# BMS_REV_A1.net
KiCad netlist of a schematic drawn in Altium Designer
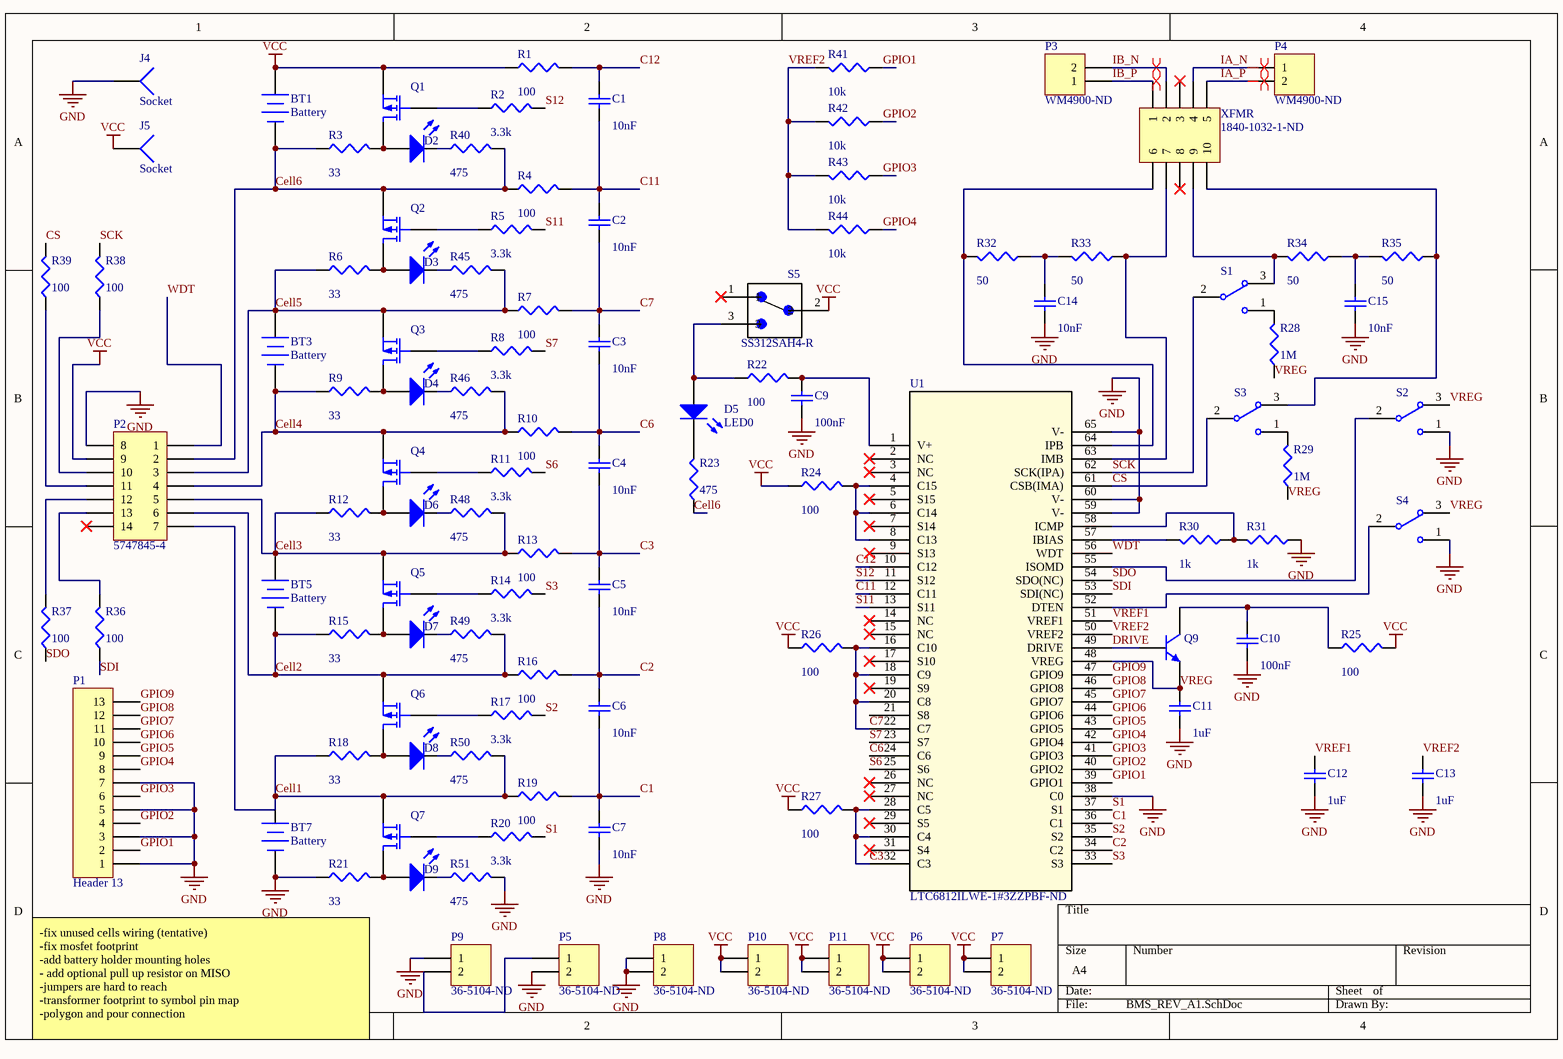
[diagram p0: BMS_REV_A1.SchDoc]

(export (version "E")
  (design (tool "Eeschema 10.0.6"))
  (components
    (comp (ref "BT1")
      (value "Battery")
      (footprint "18650 SMD:PCBComponent_1")
      (description "Multicell Battery")
      (fields (field (name "PUBLISHER") "Altium Limited"))
      (libsource (lib "Miscellaneous Devices") (part "Battery"))
    )
    (comp (ref "BT3")
      (value "Battery")
      (footprint "18650 SMD:PCBComponent_1")
      (description "Multicell Battery")
      (fields (field (name "PUBLISHER") "Altium Limited"))
      (libsource (lib "Miscellaneous Devices") (part "Battery"))
    )
    (comp (ref "BT5")
      (value "Battery")
      (footprint "18650 SMD:PCBComponent_1")
      (description "Multicell Battery")
      (fields (field (name "PUBLISHER") "Altium Limited"))
      (libsource (lib "Miscellaneous Devices") (part "Battery"))
    )
    (comp (ref "BT7")
      (value "Battery")
      (footprint "18650 SMD:PCBComponent_1")
      (description "Multicell Battery")
      (fields (field (name "PUBLISHER") "Altium Limited"))
      (libsource (lib "Miscellaneous Devices") (part "Battery"))
    )
    (comp (ref "C1")
      (value "10nF")
      (footprint "1608[0603]")
      (description "Capacitor (Semiconductor SIM Model)")
      (fields (field (name "Comment") "399-1092-1-ND") (field (name "PUBLISHER") "Altium Limited"))
      (libsource (lib "Miscellaneous Devices") (part "Cap Semi"))
    )
    (comp (ref "C2")
      (value "10nF")
      (footprint "1608[0603]")
      (description "Capacitor (Semiconductor SIM Model)")
      (fields (field (name "Comment") "399-1092-1-ND") (field (name "PUBLISHER") "Altium Limited"))
      (libsource (lib "Miscellaneous Devices") (part "Cap Semi"))
    )
    (comp (ref "C3")
      (value "10nF")
      (footprint "1608[0603]")
      (description "Capacitor (Semiconductor SIM Model)")
      (fields (field (name "Comment") "399-1092-1-ND") (field (name "PUBLISHER") "Altium Limited"))
      (libsource (lib "Miscellaneous Devices") (part "Cap Semi"))
    )
    (comp (ref "C4")
      (value "10nF")
      (footprint "1608[0603]")
      (description "Capacitor (Semiconductor SIM Model)")
      (fields (field (name "Comment") "399-1092-1-ND") (field (name "PUBLISHER") "Altium Limited"))
      (libsource (lib "Miscellaneous Devices") (part "Cap Semi"))
    )
    (comp (ref "C5")
      (value "10nF")
      (footprint "1608[0603]")
      (description "Capacitor (Semiconductor SIM Model)")
      (fields (field (name "Comment") "399-1092-1-ND") (field (name "PUBLISHER") "Altium Limited"))
      (libsource (lib "Miscellaneous Devices") (part "Cap Semi"))
    )
    (comp (ref "C6")
      (value "10nF")
      (footprint "1608[0603]")
      (description "Capacitor (Semiconductor SIM Model)")
      (fields (field (name "Comment") "399-1092-1-ND") (field (name "PUBLISHER") "Altium Limited"))
      (libsource (lib "Miscellaneous Devices") (part "Cap Semi"))
    )
    (comp (ref "C7")
      (value "10nF")
      (footprint "1608[0603]")
      (description "Capacitor (Semiconductor SIM Model)")
      (fields (field (name "Comment") "399-1092-1-ND") (field (name "PUBLISHER") "Altium Limited"))
      (libsource (lib "Miscellaneous Devices") (part "Cap Semi"))
    )
    (comp (ref "C9")
      (value "100nF")
      (footprint "6-0805_N")
      (description "Capacitor (Semiconductor SIM Model)")
      (fields (field (name "Comment") "1276-1090-1-ND") (field (name "PUBLISHER") "Altium Limited"))
      (libsource (lib "Miscellaneous Devices") (part "Cap Semi"))
    )
    (comp (ref "C10")
      (value "100nF")
      (footprint "6-0805_N")
      (description "Capacitor (Semiconductor SIM Model)")
      (fields (field (name "Comment") "1276-1090-1-ND") (field (name "PUBLISHER") "Altium Limited"))
      (libsource (lib "Miscellaneous Devices") (part "Cap Semi"))
    )
    (comp (ref "C11")
      (value "1uF")
      (footprint "6-0805_N")
      (description "Capacitor (Semiconductor SIM Model)")
      (fields (field (name "Comment") "311-3498-1-ND") (field (name "PUBLISHER") "Altium Limited"))
      (libsource (lib "Miscellaneous Devices") (part "Cap Semi"))
    )
    (comp (ref "C12")
      (value "1uF")
      (footprint "6-0805_N")
      (description "Capacitor (Semiconductor SIM Model)")
      (fields (field (name "Comment") "311-3498-1-ND") (field (name "PUBLISHER") "Altium Limited"))
      (libsource (lib "Miscellaneous Devices") (part "Cap Semi"))
    )
    (comp (ref "C13")
      (value "1uF")
      (footprint "6-0805_N")
      (description "Capacitor (Semiconductor SIM Model)")
      (fields (field (name "Comment") "311-3498-1-ND") (field (name "PUBLISHER") "Altium Limited"))
      (libsource (lib "Miscellaneous Devices") (part "Cap Semi"))
    )
    (comp (ref "C14")
      (value "10nF")
      (footprint "1608[0603]")
      (description "Capacitor (Semiconductor SIM Model)")
      (fields (field (name "Comment") "399-1092-1-ND") (field (name "PUBLISHER") "Altium Limited"))
      (libsource (lib "Miscellaneous Devices") (part "Cap Semi"))
    )
    (comp (ref "C15")
      (value "10nF")
      (footprint "1608[0603]")
      (description "Capacitor (Semiconductor SIM Model)")
      (fields (field (name "Comment") "399-1092-1-ND") (field (name "PUBLISHER") "Altium Limited"))
      (libsource (lib "Miscellaneous Devices") (part "Cap Semi"))
    )
    (comp (ref "D2")
      (value "160-1435-1-ND")
      (footprint "J1-0603")
      (description "Typical INFRARED GaAs LED")
      (fields (field (name "PUBLISHER") "Altium Limited"))
      (libsource (lib "Miscellaneous Devices") (part "LED0"))
    )
    (comp (ref "D3")
      (value "160-1435-1-ND")
      (footprint "J1-0603")
      (description "Typical INFRARED GaAs LED")
      (fields (field (name "PUBLISHER") "Altium Limited"))
      (libsource (lib "Miscellaneous Devices") (part "LED0"))
    )
    (comp (ref "D4")
      (value "160-1435-1-ND")
      (footprint "J1-0603")
      (description "Typical INFRARED GaAs LED")
      (fields (field (name "PUBLISHER") "Altium Limited"))
      (libsource (lib "Miscellaneous Devices") (part "LED0"))
    )
    (comp (ref "D5")
      (value "LED0")
      (footprint "J1-0603")
      (description "Typical INFRARED GaAs LED")
      (fields (field (name "PUBLISHER") "Altium Limited"))
      (libsource (lib "Miscellaneous Devices") (part "LED0"))
    )
    (comp (ref "D6")
      (value "160-1435-1-ND")
      (footprint "J1-0603")
      (description "Typical INFRARED GaAs LED")
      (fields (field (name "PUBLISHER") "Altium Limited"))
      (libsource (lib "Miscellaneous Devices") (part "LED0"))
    )
    (comp (ref "D7")
      (value "160-1435-1-ND")
      (footprint "J1-0603")
      (description "Typical INFRARED GaAs LED")
      (fields (field (name "PUBLISHER") "Altium Limited"))
      (libsource (lib "Miscellaneous Devices") (part "LED0"))
    )
    (comp (ref "D8")
      (value "160-1435-1-ND")
      (footprint "J1-0603")
      (description "Typical INFRARED GaAs LED")
      (fields (field (name "PUBLISHER") "Altium Limited"))
      (libsource (lib "Miscellaneous Devices") (part "LED0"))
    )
    (comp (ref "D9")
      (value "160-1435-1-ND")
      (footprint "J1-0603")
      (description "Typical INFRARED GaAs LED")
      (fields (field (name "PUBLISHER") "Altium Limited"))
      (libsource (lib "Miscellaneous Devices") (part "LED0"))
    )
    (comp (ref "J4")
      (value "Socket")
      (footprint "SMD Power Pad:PCBComponent_1")
      (fields (field (name "PUBLISHER") "Altium Limited"))
      (libsource (lib "Miscellaneous Connectors") (part "Socket"))
    )
    (comp (ref "J5")
      (value "Socket")
      (footprint "SMD Power Pad:PCBComponent_1")
      (fields (field (name "PUBLISHER") "Altium Limited"))
      (libsource (lib "Miscellaneous Connectors") (part "Socket"))
    )
    (comp (ref "P1")
      (value "Header 13")
      (footprint "SMD Finger Pads:PCBComponent_1")
      (description "Header, 13-Pin")
      (fields (field (name "PUBLISHER") "Altium Limited"))
      (libsource (lib "Miscellaneous Connectors") (part "Header 13"))
    )
    (comp (ref "P2")
      (value "5747845-4")
      (footprint "*5747845-4")
      (description "Header, 7-Pin, Dual row")
      (fields (field (name "PUBLISHER") "Altium Limited"))
      (libsource (lib "Miscellaneous Connectors") (part "Header 7X2A"))
    )
    (comp (ref "P3")
      (value "WM4900-ND")
      (footprint "Molex Connectors:WM4900-ND")
      (description "Header, 2-Pin")
      (fields (field (name "PUBLISHER") "Altium Limited"))
      (libsource (lib "") (part "Header 2_1"))
    )
    (comp (ref "P4")
      (value "WM4900-ND")
      (footprint "Molex Connectors:WM4900-ND")
      (description "Header, 2-Pin")
      (fields (field (name "PUBLISHER") "Altium Limited"))
      (libsource (lib "Miscellaneous Connectors") (part "Header 2"))
    )
    (comp (ref "P5")
      (value "36-5104-ND")
      (footprint "5104:PCBComponent_1")
      (description "Header, 2-Pin")
      (fields (field (name "PUBLISHER") "Altium Limited"))
      (libsource (lib "Miscellaneous Connectors") (part "Header 2"))
    )
    (comp (ref "P6")
      (value "36-5104-ND")
      (footprint "5104:PCBComponent_1")
      (description "Header, 2-Pin")
      (fields (field (name "PUBLISHER") "Altium Limited"))
      (libsource (lib "Miscellaneous Connectors") (part "Header 2"))
    )
    (comp (ref "P7")
      (value "36-5104-ND")
      (footprint "5104:PCBComponent_1")
      (description "Header, 2-Pin")
      (fields (field (name "PUBLISHER") "Altium Limited"))
      (libsource (lib "Miscellaneous Connectors") (part "Header 2"))
    )
    (comp (ref "P8")
      (value "36-5104-ND")
      (footprint "5104:PCBComponent_1")
      (description "Header, 2-Pin")
      (fields (field (name "PUBLISHER") "Altium Limited"))
      (libsource (lib "Miscellaneous Connectors") (part "Header 2"))
    )
    (comp (ref "P9")
      (value "36-5104-ND")
      (footprint "5104:PCBComponent_1")
      (description "Header, 2-Pin")
      (fields (field (name "PUBLISHER") "Altium Limited"))
      (libsource (lib "Miscellaneous Connectors") (part "Header 2"))
    )
    (comp (ref "P10")
      (value "36-5104-ND")
      (footprint "5104:PCBComponent_1")
      (description "Header, 2-Pin")
      (fields (field (name "PUBLISHER") "Altium Limited"))
      (libsource (lib "Miscellaneous Connectors") (part "Header 2"))
    )
    (comp (ref "P11")
      (value "36-5104-ND")
      (footprint "5104:PCBComponent_1")
      (description "Header, 2-Pin")
      (fields (field (name "PUBLISHER") "Altium Limited"))
      (libsource (lib "Miscellaneous Connectors") (part "Header 2"))
    )
    (comp (ref "Q1")
      (value "BSS308PEH6327XTSA1CT-ND")
      (footprint "SOT95P245X110-3N")
      (description "P-Channel MOSFET")
      (fields (field (name "PUBLISHER") "Altium Limited"))
      (libsource (lib "Miscellaneous Devices") (part "MOSFET-P"))
    )
    (comp (ref "Q2")
      (value "BSS308PEH6327XTSA1CT-ND")
      (footprint "SOT95P245X110-3N")
      (description "P-Channel MOSFET")
      (fields (field (name "PUBLISHER") "Altium Limited"))
      (libsource (lib "Miscellaneous Devices") (part "MOSFET-P"))
    )
    (comp (ref "Q3")
      (value "BSS308PEH6327XTSA1CT-ND")
      (footprint "SOT95P245X110-3N")
      (description "P-Channel MOSFET")
      (fields (field (name "PUBLISHER") "Altium Limited"))
      (libsource (lib "Miscellaneous Devices") (part "MOSFET-P"))
    )
    (comp (ref "Q4")
      (value "BSS308PEH6327XTSA1CT-ND")
      (footprint "SOT95P245X110-3N")
      (description "P-Channel MOSFET")
      (fields (field (name "PUBLISHER") "Altium Limited"))
      (libsource (lib "Miscellaneous Devices") (part "MOSFET-P"))
    )
    (comp (ref "Q5")
      (value "BSS308PEH6327XTSA1CT-ND")
      (footprint "SOT95P245X110-3N")
      (description "P-Channel MOSFET")
      (fields (field (name "PUBLISHER") "Altium Limited"))
      (libsource (lib "Miscellaneous Devices") (part "MOSFET-P"))
    )
    (comp (ref "Q6")
      (value "BSS308PEH6327XTSA1CT-ND")
      (footprint "SOT95P245X110-3N")
      (description "P-Channel MOSFET")
      (fields (field (name "PUBLISHER") "Altium Limited"))
      (libsource (lib "Miscellaneous Devices") (part "MOSFET-P"))
    )
    (comp (ref "Q7")
      (value "BSS308PEH6327XTSA1CT-ND")
      (footprint "SOT95P245X110-3N")
      (description "P-Channel MOSFET")
      (fields (field (name "PUBLISHER") "Altium Limited"))
      (libsource (lib "Miscellaneous Devices") (part "MOSFET-P"))
    )
    (comp (ref "Q9")
      (value "DXT5551P5-13CT-ND")
      (footprint "DXT5551P5-13")
      (description "NPN General Purpose Amplifier")
      (fields (field (name "PUBLISHER") "Altium Limited"))
      (libsource (lib "Miscellaneous Devices") (part "2N3904"))
    )
    (comp (ref "R1")
      (value "100")
      (footprint "J1-0603")
      (description "Resistor")
      (fields (field (name "Comment") "A129676CT-ND") (field (name "PUBLISHER") "Altium Limited"))
      (libsource (lib "Miscellaneous Devices") (part "Res3"))
    )
    (comp (ref "R2")
      (value "3.3k")
      (footprint "J1-0603")
      (description "Resistor")
      (fields (field (name "Comment") "A129543CT-ND") (field (name "PUBLISHER") "Altium Limited"))
      (libsource (lib "Miscellaneous Devices") (part "Res3"))
    )
    (comp (ref "R3")
      (value "33")
      (footprint "12Z-2010")
      (description "Resistor")
      (fields (field (name "Comment") "A130642CT-ND") (field (name "PUBLISHER") "Altium Limited"))
      (libsource (lib "Miscellaneous Devices") (part "Res3"))
    )
    (comp (ref "R4")
      (value "100")
      (footprint "J1-0603")
      (description "Resistor")
      (fields (field (name "Comment") "A129676CT-ND") (field (name "PUBLISHER") "Altium Limited"))
      (libsource (lib "Miscellaneous Devices") (part "Res3"))
    )
    (comp (ref "R5")
      (value "3.3k")
      (footprint "J1-0603")
      (description "Resistor")
      (fields (field (name "Comment") "A129543CT-ND") (field (name "PUBLISHER") "Altium Limited"))
      (libsource (lib "Miscellaneous Devices") (part "Res3"))
    )
    (comp (ref "R6")
      (value "33")
      (footprint "12Z-2010")
      (description "Resistor")
      (fields (field (name "Comment") "A130642CT-ND") (field (name "PUBLISHER") "Altium Limited"))
      (libsource (lib "Miscellaneous Devices") (part "Res3"))
    )
    (comp (ref "R7")
      (value "100")
      (footprint "J1-0603")
      (description "Resistor")
      (fields (field (name "Comment") "A129676CT-ND") (field (name "PUBLISHER") "Altium Limited"))
      (libsource (lib "Miscellaneous Devices") (part "Res3"))
    )
    (comp (ref "R8")
      (value "3.3k")
      (footprint "J1-0603")
      (description "Resistor")
      (fields (field (name "Comment") "A129543CT-ND") (field (name "PUBLISHER") "Altium Limited"))
      (libsource (lib "Miscellaneous Devices") (part "Res3"))
    )
    (comp (ref "R9")
      (value "33")
      (footprint "12Z-2010")
      (description "Resistor")
      (fields (field (name "Comment") "A130642CT-ND") (field (name "PUBLISHER") "Altium Limited"))
      (libsource (lib "Miscellaneous Devices") (part "Res3"))
    )
    (comp (ref "R10")
      (value "100")
      (footprint "J1-0603")
      (description "Resistor")
      (fields (field (name "Comment") "A129676CT-ND") (field (name "PUBLISHER") "Altium Limited"))
      (libsource (lib "Miscellaneous Devices") (part "Res3"))
    )
    (comp (ref "R11")
      (value "3.3k")
      (footprint "J1-0603")
      (description "Resistor")
      (fields (field (name "Comment") "A129543CT-ND") (field (name "PUBLISHER") "Altium Limited"))
      (libsource (lib "Miscellaneous Devices") (part "Res3"))
    )
    (comp (ref "R12")
      (value "33")
      (footprint "12Z-2010")
      (description "Resistor")
      (fields (field (name "Comment") "A130642CT-ND") (field (name "PUBLISHER") "Altium Limited"))
      (libsource (lib "Miscellaneous Devices") (part "Res3"))
    )
    (comp (ref "R13")
      (value "100")
      (footprint "J1-0603")
      (description "Resistor")
      (fields (field (name "Comment") "A129676CT-ND") (field (name "PUBLISHER") "Altium Limited"))
      (libsource (lib "Miscellaneous Devices") (part "Res3"))
    )
    (comp (ref "R14")
      (value "3.3k")
      (footprint "J1-0603")
      (description "Resistor")
      (fields (field (name "Comment") "A129543CT-ND") (field (name "PUBLISHER") "Altium Limited"))
      (libsource (lib "Miscellaneous Devices") (part "Res3"))
    )
    (comp (ref "R15")
      (value "33")
      (footprint "12Z-2010")
      (description "Resistor")
      (fields (field (name "Comment") "A130642CT-ND") (field (name "PUBLISHER") "Altium Limited"))
      (libsource (lib "Miscellaneous Devices") (part "Res3"))
    )
    (comp (ref "R16")
      (value "100")
      (footprint "J1-0603")
      (description "Resistor")
      (fields (field (name "Comment") "A129676CT-ND") (field (name "PUBLISHER") "Altium Limited"))
      (libsource (lib "Miscellaneous Devices") (part "Res3"))
    )
    (comp (ref "R17")
      (value "3.3k")
      (footprint "J1-0603")
      (description "Resistor")
      (fields (field (name "Comment") "A129543CT-ND") (field (name "PUBLISHER") "Altium Limited"))
      (libsource (lib "Miscellaneous Devices") (part "Res3"))
    )
    (comp (ref "R18")
      (value "33")
      (footprint "12Z-2010")
      (description "Resistor")
      (fields (field (name "Comment") "A130642CT-ND") (field (name "PUBLISHER") "Altium Limited"))
      (libsource (lib "Miscellaneous Devices") (part "Res3"))
    )
    (comp (ref "R19")
      (value "100")
      (footprint "J1-0603")
      (description "Resistor")
      (fields (field (name "Comment") "A129676CT-ND") (field (name "PUBLISHER") "Altium Limited"))
      (libsource (lib "Miscellaneous Devices") (part "Res3"))
    )
    (comp (ref "R20")
      (value "3.3k")
      (footprint "J1-0603")
      (description "Resistor")
      (fields (field (name "Comment") "A129543CT-ND") (field (name "PUBLISHER") "Altium Limited"))
      (libsource (lib "Miscellaneous Devices") (part "Res3"))
    )
    (comp (ref "R21")
      (value "33")
      (footprint "12Z-2010")
      (description "Resistor")
      (fields (field (name "Comment") "A130642CT-ND") (field (name "PUBLISHER") "Altium Limited"))
      (libsource (lib "Miscellaneous Devices") (part "Res3"))
    )
    (comp (ref "R22")
      (value "100")
      (footprint "J1-0603")
      (description "Resistor")
      (fields (field (name "Comment") "A129676CT-ND") (field (name "PUBLISHER") "Altium Limited"))
      (libsource (lib "Miscellaneous Devices") (part "Res3"))
    )
    (comp (ref "R23")
      (value "475")
      (footprint "J1-0603")
      (description "Resistor")
      (fields (field (name "Comment") "RMCF2010JT33R0CT-ND") (field (name "PUBLISHER") "Altium Limited"))
      (libsource (lib "Miscellaneous Devices") (part "Res3"))
    )
    (comp (ref "R24")
      (value "100")
      (footprint "J1-0603")
      (description "Resistor")
      (fields (field (name "Comment") "A129676CT-ND") (field (name "PUBLISHER") "Altium Limited"))
      (libsource (lib "Miscellaneous Devices") (part "Res3"))
    )
    (comp (ref "R25")
      (value "100")
      (footprint "J1-0603")
      (description "Resistor")
      (fields (field (name "Comment") "A129676CT-ND") (field (name "PUBLISHER") "Altium Limited"))
      (libsource (lib "Miscellaneous Devices") (part "Res3"))
    )
    (comp (ref "R26")
      (value "100")
      (footprint "J1-0603")
      (description "Resistor")
      (fields (field (name "Comment") "A129676CT-ND") (field (name "PUBLISHER") "Altium Limited"))
      (libsource (lib "Miscellaneous Devices") (part "Res3"))
    )
    (comp (ref "R27")
      (value "100")
      (footprint "J1-0603")
      (description "Resistor")
      (fields (field (name "Comment") "A129676CT-ND") (field (name "PUBLISHER") "Altium Limited"))
      (libsource (lib "Miscellaneous Devices") (part "Res3"))
    )
    (comp (ref "R28")
      (value "1M")
      (footprint "J1-0603")
      (description "Resistor")
      (fields (field (name "Comment") "A129724CT-ND") (field (name "PUBLISHER") "Altium Limited"))
      (libsource (lib "Miscellaneous Devices") (part "Res3"))
    )
    (comp (ref "R29")
      (value "1M")
      (footprint "J1-0603")
      (description "Resistor")
      (fields (field (name "Comment") "A129724CT-ND") (field (name "PUBLISHER") "Altium Limited"))
      (libsource (lib "Miscellaneous Devices") (part "Res3"))
    )
    (comp (ref "R30")
      (value "1k")
      (footprint "J1-0603")
      (description "Resistor")
      (fields (field (name "Comment") "RNCP0603FTD1K00CT-ND") (field (name "PUBLISHER") "Altium Limited"))
      (libsource (lib "Miscellaneous Devices") (part "Res3"))
    )
    (comp (ref "R31")
      (value "1k")
      (footprint "J1-0603")
      (description "Resistor")
      (fields (field (name "Comment") "RNCP0603FTD1K00CT-ND") (field (name "PUBLISHER") "Altium Limited"))
      (libsource (lib "Miscellaneous Devices") (part "Res3"))
    )
    (comp (ref "R32")
      (value "50")
      (footprint "J1-0603")
      (description "Resistor")
      (fields (field (name "Comment") "311-2598-1-ND") (field (name "PUBLISHER") "Altium Limited"))
      (libsource (lib "Miscellaneous Devices") (part "Res3"))
    )
    (comp (ref "R33")
      (value "50")
      (footprint "J1-0603")
      (description "Resistor")
      (fields (field (name "Comment") "311-2598-1-ND") (field (name "PUBLISHER") "Altium Limited"))
      (libsource (lib "Miscellaneous Devices") (part "Res3"))
    )
    (comp (ref "R34")
      (value "50")
      (footprint "J1-0603")
      (description "Resistor")
      (fields (field (name "Comment") "311-2598-1-ND") (field (name "PUBLISHER") "Altium Limited"))
      (libsource (lib "Miscellaneous Devices") (part "Res3"))
    )
    (comp (ref "R35")
      (value "50")
      (footprint "J1-0603")
      (description "Resistor")
      (fields (field (name "Comment") "311-2598-1-ND") (field (name "PUBLISHER") "Altium Limited"))
      (libsource (lib "Miscellaneous Devices") (part "Res3"))
    )
    (comp (ref "R36")
      (value "100")
      (footprint "J1-0603")
      (description "Resistor")
      (fields (field (name "Comment") "A129676CT-ND") (field (name "PUBLISHER") "Altium Limited"))
      (libsource (lib "Miscellaneous Devices") (part "Res3"))
    )
    (comp (ref "R37")
      (value "100")
      (footprint "J1-0603")
      (description "Resistor")
      (fields (field (name "Comment") "A129676CT-ND") (field (name "PUBLISHER") "Altium Limited"))
      (libsource (lib "Miscellaneous Devices") (part "Res3"))
    )
    (comp (ref "R38")
      (value "100")
      (footprint "J1-0603")
      (description "Resistor")
      (fields (field (name "Comment") "A129676CT-ND") (field (name "PUBLISHER") "Altium Limited"))
      (libsource (lib "Miscellaneous Devices") (part "Res3"))
    )
    (comp (ref "R39")
      (value "100")
      (footprint "J1-0603")
      (description "Resistor")
      (fields (field (name "Comment") "A129676CT-ND") (field (name "PUBLISHER") "Altium Limited"))
      (libsource (lib "Miscellaneous Devices") (part "Res3"))
    )
    (comp (ref "R40")
      (value "475")
      (footprint "J1-0603")
      (description "Resistor")
      (fields (field (name "Comment") "RMCF2010JT33R0CT-ND") (field (name "PUBLISHER") "Altium Limited"))
      (libsource (lib "Miscellaneous Devices") (part "Res3"))
    )
    (comp (ref "R41")
      (value "10k")
      (footprint "J1-0603")
      (description "Resistor")
      (fields (field (name "Comment") "RNCP0603FTD10K0CT-ND") (field (name "PUBLISHER") "Altium Limited"))
      (libsource (lib "Miscellaneous Devices") (part "Res3"))
    )
    (comp (ref "R42")
      (value "10k")
      (footprint "J1-0603")
      (description "Resistor")
      (fields (field (name "Comment") "RNCP0603FTD10K0CT-ND") (field (name "PUBLISHER") "Altium Limited"))
      (libsource (lib "Miscellaneous Devices") (part "Res3"))
    )
    (comp (ref "R43")
      (value "10k")
      (footprint "J1-0603")
      (description "Resistor")
      (fields (field (name "Comment") "RNCP0603FTD10K0CT-ND") (field (name "PUBLISHER") "Altium Limited"))
      (libsource (lib "Miscellaneous Devices") (part "Res3"))
    )
    (comp (ref "R44")
      (value "10k")
      (footprint "J1-0603")
      (description "Resistor")
      (fields (field (name "Comment") "RNCP0603FTD10K0CT-ND") (field (name "PUBLISHER") "Altium Limited"))
      (libsource (lib "Miscellaneous Devices") (part "Res3"))
    )
    (comp (ref "R45")
      (value "475")
      (footprint "J1-0603")
      (description "Resistor")
      (fields (field (name "Comment") "RMCF2010JT33R0CT-ND") (field (name "PUBLISHER") "Altium Limited"))
      (libsource (lib "Miscellaneous Devices") (part "Res3"))
    )
    (comp (ref "R46")
      (value "475")
      (footprint "J1-0603")
      (description "Resistor")
      (fields (field (name "Comment") "RMCF2010JT33R0CT-ND") (field (name "PUBLISHER") "Altium Limited"))
      (libsource (lib "Miscellaneous Devices") (part "Res3"))
    )
    (comp (ref "R48")
      (value "475")
      (footprint "J1-0603")
      (description "Resistor")
      (fields (field (name "Comment") "RMCF2010JT33R0CT-ND") (field (name "PUBLISHER") "Altium Limited"))
      (libsource (lib "Miscellaneous Devices") (part "Res3"))
    )
    (comp (ref "R49")
      (value "475")
      (footprint "J1-0603")
      (description "Resistor")
      (fields (field (name "Comment") "RMCF2010JT33R0CT-ND") (field (name "PUBLISHER") "Altium Limited"))
      (libsource (lib "Miscellaneous Devices") (part "Res3"))
    )
    (comp (ref "R50")
      (value "475")
      (footprint "J1-0603")
      (description "Resistor")
      (fields (field (name "Comment") "RMCF2010JT33R0CT-ND") (field (name "PUBLISHER") "Altium Limited"))
      (libsource (lib "Miscellaneous Devices") (part "Res3"))
    )
    (comp (ref "R51")
      (value "475")
      (footprint "J1-0603")
      (description "Resistor")
      (fields (field (name "Comment") "RMCF2010JT33R0CT-ND") (field (name "PUBLISHER") "Altium Limited"))
      (libsource (lib "Miscellaneous Devices") (part "Res3"))
    )
    (comp (ref "S1")
      (value "S9337-ND, SAM8981-ND")
      (footprint "*TSM-103-01-L-SV")
      (description "SPDT Subminiature Toggle Switch, Right Angle Mounting, Vertical Actuation")
      (fields (field (name "PUBLISHER") "Altium Limited"))
      (libsource (lib "Miscellaneous Devices") (part "SW-SPDT"))
    )
    (comp (ref "S2")
      (value "S9337-ND, SAM8981-ND")
      (footprint "*TSM-103-01-L-SV")
      (description "SPDT Subminiature Toggle Switch, Right Angle Mounting, Vertical Actuation")
      (fields (field (name "PUBLISHER") "Altium Limited"))
      (libsource (lib "Miscellaneous Devices") (part "SW-SPDT"))
    )
    (comp (ref "S3")
      (value "S9337-ND, SAM8981-ND")
      (footprint "*TSM-103-01-L-SV")
      (description "SPDT Subminiature Toggle Switch, Right Angle Mounting, Vertical Actuation")
      (fields (field (name "PUBLISHER") "Altium Limited"))
      (libsource (lib "Miscellaneous Devices") (part "SW-SPDT"))
    )
    (comp (ref "S4")
      (value "S9337-ND, SAM8981-ND")
      (footprint "*TSM-103-01-L-SV")
      (description "SPDT Subminiature Toggle Switch, Right Angle Mounting, Vertical Actuation")
      (fields (field (name "PUBLISHER") "Altium Limited"))
      (libsource (lib "Miscellaneous Devices") (part "SW-SPDT"))
    )
    (comp (ref "S5")
      (value "SS312SAH4-R")
      (footprint "*SW_SS312SAH4-R")
      (description "Switch Slide ON None ON SPDT Side Slide 0.1A 28VAC 28VDC 0.4VA 10000Cycles Gull Wing SMD T/R")
      (fields (field (name "MF") "NKK Switches"))
      (libsource (lib "SS312SAH4-R") (part "SS312SAH4-R"))
    )
    (comp (ref "U1")
      (value "LTC6812ILWE-1#3ZZPBF-ND")
      (footprint "LQFP64_LWE_A - duplicate")
      (description "No Description Available")
      (fields (field (name "COPYRIGHT") "Copyright (C) 2018 Accelerated Designs. All rights reserved"))
      (libsource (lib "LTC6812") (part "LTC6812HLWE-1"))
    )
    (comp (ref "XFMR")
      (value "1840-1032-1-ND")
      (footprint "HM2100NLT")
      (description "Header, 5-Pin, Dual row\r\nHM2100NLT")
      (fields (field (name "PUBLISHER") "Altium Limited"))
      (libsource (lib "Miscellaneous Connectors") (part "Header 5X2A"))
    )
  )
  (nets
    (net (code "1") (name "/C1") (class "Default")
      (node (ref "C6") (pin "1") (pinfunction "1_1") (pintype "passive"))
      (node (ref "C7") (pin "2") (pinfunction "2_2") (pintype "passive"))
      (node (ref "R19") (pin "2") (pinfunction "2_2") (pintype "passive"))
      (node (ref "U1") (pin "36") (pinfunction "C1_36") (pintype "passive"))
    )
    (net (code "2") (name "/C2") (class "Default")
      (node (ref "C5") (pin "1") (pinfunction "1_1") (pintype "passive"))
      (node (ref "C6") (pin "2") (pinfunction "2_2") (pintype "passive"))
      (node (ref "R16") (pin "2") (pinfunction "2_2") (pintype "passive"))
      (node (ref "U1") (pin "34") (pinfunction "C2_34") (pintype "passive"))
    )
    (net (code "3") (name "/C3") (class "Default")
      (node (ref "C4") (pin "1") (pinfunction "1_1") (pintype "passive"))
      (node (ref "C5") (pin "2") (pinfunction "2_2") (pintype "passive"))
      (node (ref "R13") (pin "2") (pinfunction "2_2") (pintype "passive"))
      (node (ref "R27") (pin "2") (pinfunction "2_2") (pintype "passive"))
      (node (ref "U1") (pin "28") (pinfunction "C5_28") (pintype "passive"))
      (node (ref "U1") (pin "30") (pinfunction "C4_30") (pintype "passive"))
      (node (ref "U1") (pin "32") (pinfunction "C3_32") (pintype "passive"))
    )
    (net (code "4") (name "/C6") (class "Default")
      (node (ref "C3") (pin "1") (pinfunction "1_1") (pintype "passive"))
      (node (ref "C4") (pin "2") (pinfunction "2_2") (pintype "passive"))
      (node (ref "R10") (pin "2") (pinfunction "2_2") (pintype "passive"))
      (node (ref "U1") (pin "24") (pinfunction "C6_24") (pintype "passive"))
    )
    (net (code "5") (name "/C7") (class "Default")
      (node (ref "C2") (pin "1") (pinfunction "1_1") (pintype "passive"))
      (node (ref "C3") (pin "2") (pinfunction "2_2") (pintype "passive"))
      (node (ref "R26") (pin "2") (pinfunction "2_2") (pintype "passive"))
      (node (ref "R7") (pin "2") (pinfunction "2_2") (pintype "passive"))
      (node (ref "U1") (pin "16") (pinfunction "C10_16") (pintype "passive"))
      (node (ref "U1") (pin "18") (pinfunction "C9_18") (pintype "passive"))
      (node (ref "U1") (pin "20") (pinfunction "C8_20") (pintype "passive"))
      (node (ref "U1") (pin "22") (pinfunction "C7_22") (pintype "passive"))
    )
    (net (code "6") (name "/C11") (class "Default")
      (node (ref "C1") (pin "1") (pinfunction "1_1") (pintype "passive"))
      (node (ref "C2") (pin "2") (pinfunction "2_2") (pintype "passive"))
      (node (ref "R4") (pin "2") (pinfunction "2_2") (pintype "passive"))
      (node (ref "U1") (pin "12") (pinfunction "C11_12") (pintype "passive"))
    )
    (net (code "7") (name "/C12") (class "Default")
      (node (ref "C1") (pin "2") (pinfunction "2_2") (pintype "passive"))
      (node (ref "R1") (pin "2") (pinfunction "2_2") (pintype "passive"))
      (node (ref "U1") (pin "10") (pinfunction "C12_10") (pintype "passive"))
    )
    (net (code "8") (name "/CS") (class "Default")
      (node (ref "R39") (pin "1") (pinfunction "1_1") (pintype "passive"))
      (node (ref "S3") (pin "2") (pinfunction "2_2") (pintype "passive"))
      (node (ref "U1") (pin "61") (pinfunction "CSB(IMA)_61") (pintype "passive"))
    )
    (net (code "9") (name "/Cell1") (class "Default")
      (node (ref "BT7") (pin "1") (pinfunction "+_1") (pintype "passive"))
      (node (ref "P2") (pin "7") (pinfunction "7_7") (pintype "passive"))
      (node (ref "Q7") (pin "3") (pinfunction "S_3") (pintype "passive"))
      (node (ref "R18") (pin "2") (pinfunction "2_2") (pintype "passive"))
      (node (ref "R19") (pin "1") (pinfunction "1_1") (pintype "passive"))
      (node (ref "R50") (pin "1") (pinfunction "1_1") (pintype "passive"))
    )
    (net (code "10") (name "/Cell2") (class "Default")
      (node (ref "BT5") (pin "2") (pinfunction "-_2") (pintype "passive"))
      (node (ref "P2") (pin "6") (pinfunction "6_6") (pintype "passive"))
      (node (ref "Q6") (pin "3") (pinfunction "S_3") (pintype "passive"))
      (node (ref "R15") (pin "2") (pinfunction "2_2") (pintype "passive"))
      (node (ref "R16") (pin "1") (pinfunction "1_1") (pintype "passive"))
      (node (ref "R49") (pin "1") (pinfunction "1_1") (pintype "passive"))
    )
    (net (code "11") (name "/Cell3") (class "Default")
      (node (ref "BT5") (pin "1") (pinfunction "+_1") (pintype "passive"))
      (node (ref "P2") (pin "5") (pinfunction "5_5") (pintype "passive"))
      (node (ref "Q5") (pin "3") (pinfunction "S_3") (pintype "passive"))
      (node (ref "R12") (pin "2") (pinfunction "2_2") (pintype "passive"))
      (node (ref "R13") (pin "1") (pinfunction "1_1") (pintype "passive"))
      (node (ref "R48") (pin "1") (pinfunction "1_1") (pintype "passive"))
    )
    (net (code "12") (name "/Cell4") (class "Default")
      (node (ref "BT3") (pin "2") (pinfunction "-_2") (pintype "passive"))
      (node (ref "P2") (pin "4") (pinfunction "4_4") (pintype "passive"))
      (node (ref "Q4") (pin "3") (pinfunction "S_3") (pintype "passive"))
      (node (ref "R10") (pin "1") (pinfunction "1_1") (pintype "passive"))
      (node (ref "R46") (pin "1") (pinfunction "1_1") (pintype "passive"))
      (node (ref "R9") (pin "2") (pinfunction "2_2") (pintype "passive"))
    )
    (net (code "13") (name "/Cell5") (class "Default")
      (node (ref "BT3") (pin "1") (pinfunction "+_1") (pintype "passive"))
      (node (ref "P2") (pin "3") (pinfunction "3_3") (pintype "passive"))
      (node (ref "Q3") (pin "3") (pinfunction "S_3") (pintype "passive"))
      (node (ref "R45") (pin "1") (pinfunction "1_1") (pintype "passive"))
      (node (ref "R6") (pin "2") (pinfunction "2_2") (pintype "passive"))
      (node (ref "R7") (pin "1") (pinfunction "1_1") (pintype "passive"))
    )
    (net (code "14") (name "/Cell6") (class "Default")
      (node (ref "BT1") (pin "2") (pinfunction "-_2") (pintype "passive"))
      (node (ref "P2") (pin "2") (pinfunction "2_2") (pintype "passive"))
      (node (ref "Q2") (pin "3") (pinfunction "S_3") (pintype "passive"))
      (node (ref "R23") (pin "2") (pinfunction "2_2") (pintype "passive"))
      (node (ref "R3") (pin "2") (pinfunction "2_2") (pintype "passive"))
      (node (ref "R4") (pin "1") (pinfunction "1_1") (pintype "passive"))
      (node (ref "R40") (pin "1") (pinfunction "1_1") (pintype "passive"))
    )
    (net (code "15") (name "/DRIVE") (class "Default")
      (node (ref "Q9") (pin "2") (pinfunction "B_2") (pintype "passive"))
      (node (ref "U1") (pin "49") (pinfunction "DRIVE_49") (pintype "passive"))
    )
    (net (code "16") (name "/GPIO1") (class "Default")
      (node (ref "P1") (pin "2") (pinfunction "2_2") (pintype "passive"))
      (node (ref "R41") (pin "2") (pinfunction "2_2") (pintype "passive"))
      (node (ref "U1") (pin "39") (pinfunction "GPIO1_39") (pintype "passive"))
    )
    (net (code "17") (name "/GPIO2") (class "Default")
      (node (ref "P1") (pin "4") (pinfunction "4_4") (pintype "passive"))
      (node (ref "R42") (pin "2") (pinfunction "2_2") (pintype "passive"))
      (node (ref "U1") (pin "40") (pinfunction "GPIO2_40") (pintype "passive"))
    )
    (net (code "18") (name "/GPIO3") (class "Default")
      (node (ref "P1") (pin "6") (pinfunction "6_6") (pintype "passive"))
      (node (ref "R43") (pin "2") (pinfunction "2_2") (pintype "passive"))
      (node (ref "U1") (pin "41") (pinfunction "GPIO3_41") (pintype "passive"))
    )
    (net (code "19") (name "/GPIO4") (class "Default")
      (node (ref "P1") (pin "8") (pinfunction "8_8") (pintype "passive"))
      (node (ref "R44") (pin "2") (pinfunction "2_2") (pintype "passive"))
      (node (ref "U1") (pin "42") (pinfunction "GPIO4_42") (pintype "passive"))
    )
    (net (code "20") (name "/GPIO5") (class "Default")
      (node (ref "P1") (pin "9") (pinfunction "9_9") (pintype "passive"))
      (node (ref "U1") (pin "43") (pinfunction "GPIO5_43") (pintype "passive"))
    )
    (net (code "21") (name "/GPIO6") (class "Default")
      (node (ref "P1") (pin "10") (pinfunction "10_10") (pintype "passive"))
      (node (ref "U1") (pin "44") (pinfunction "GPIO6_44") (pintype "passive"))
    )
    (net (code "22") (name "/GPIO7") (class "Default")
      (node (ref "P1") (pin "11") (pinfunction "11_11") (pintype "passive"))
      (node (ref "U1") (pin "45") (pinfunction "GPIO7_45") (pintype "passive"))
    )
    (net (code "23") (name "/GPIO8") (class "Default")
      (node (ref "P1") (pin "12") (pinfunction "12_12") (pintype "passive"))
      (node (ref "U1") (pin "46") (pinfunction "GPIO8_46") (pintype "passive"))
    )
    (net (code "24") (name "/GPIO9") (class "Default")
      (node (ref "P1") (pin "13") (pinfunction "13_13") (pintype "passive"))
      (node (ref "U1") (pin "47") (pinfunction "GPIO9_47") (pintype "passive"))
    )
    (net (code "25") (name "/IA_N") (class "Default")
      (node (ref "P4") (pin "1") (pinfunction "1_1") (pintype "passive"))
      (node (ref "XFMR") (pin "4") (pinfunction "4_4") (pintype "passive"))
    )
    (net (code "26") (name "/IA_P") (class "Default")
      (node (ref "P4") (pin "2") (pinfunction "2_2") (pintype "passive"))
      (node (ref "XFMR") (pin "5") (pinfunction "5_5") (pintype "passive"))
    )
    (net (code "27") (name "/IB_N") (class "Default")
      (node (ref "P3") (pin "2") (pinfunction "2_2") (pintype "passive"))
      (node (ref "XFMR") (pin "2") (pinfunction "2_2") (pintype "passive"))
    )
    (net (code "28") (name "/IB_P") (class "Default")
      (node (ref "P3") (pin "1") (pinfunction "1_1") (pintype "passive"))
      (node (ref "XFMR") (pin "1") (pinfunction "1_1") (pintype "passive"))
    )
    (net (code "29") (name "/S1") (class "Default")
      (node (ref "R20") (pin "2") (pinfunction "2_2") (pintype "passive"))
      (node (ref "U1") (pin "37") (pinfunction "S1_37") (pintype "passive"))
    )
    (net (code "30") (name "/S2") (class "Default")
      (node (ref "R17") (pin "2") (pinfunction "2_2") (pintype "passive"))
      (node (ref "U1") (pin "35") (pinfunction "S2_35") (pintype "passive"))
    )
    (net (code "31") (name "/S3") (class "Default")
      (node (ref "R14") (pin "2") (pinfunction "2_2") (pintype "passive"))
      (node (ref "U1") (pin "33") (pinfunction "S3_33") (pintype "passive"))
    )
    (net (code "32") (name "/S6") (class "Default")
      (node (ref "R11") (pin "2") (pinfunction "2_2") (pintype "passive"))
      (node (ref "U1") (pin "25") (pinfunction "S6_25") (pintype "passive"))
    )
    (net (code "33") (name "/S7") (class "Default")
      (node (ref "R8") (pin "2") (pinfunction "2_2") (pintype "passive"))
      (node (ref "U1") (pin "23") (pinfunction "S7_23") (pintype "passive"))
    )
    (net (code "34") (name "/S11") (class "Default")
      (node (ref "R5") (pin "2") (pinfunction "2_2") (pintype "passive"))
      (node (ref "U1") (pin "13") (pinfunction "S11_13") (pintype "passive"))
    )
    (net (code "35") (name "/S12") (class "Default")
      (node (ref "R2") (pin "2") (pinfunction "2_2") (pintype "passive"))
      (node (ref "U1") (pin "11") (pinfunction "S12_11") (pintype "passive"))
    )
    (net (code "36") (name "/SCK") (class "Default")
      (node (ref "R38") (pin "1") (pinfunction "1_1") (pintype "passive"))
      (node (ref "S1") (pin "2") (pinfunction "2_2") (pintype "passive"))
      (node (ref "U1") (pin "62") (pinfunction "SCK(IPA)_62") (pintype "passive"))
    )
    (net (code "37") (name "/SDI") (class "Default")
      (node (ref "R36") (pin "2") (pinfunction "2_2") (pintype "passive"))
      (node (ref "U1") (pin "53") (pinfunction "SDI(NC)_53") (pintype "passive"))
    )
    (net (code "38") (name "/SDO") (class "Default")
      (node (ref "R37") (pin "2") (pinfunction "2_2") (pintype "passive"))
      (node (ref "U1") (pin "54") (pinfunction "SDO(NC)_54") (pintype "passive"))
    )
    (net (code "39") (name "/VREF1") (class "Default")
      (node (ref "C12") (pin "2") (pinfunction "2_2") (pintype "passive"))
      (node (ref "U1") (pin "51") (pinfunction "VREF1_51") (pintype "passive"))
    )
    (net (code "40") (name "/VREF2") (class "Default")
      (node (ref "C13") (pin "2") (pinfunction "2_2") (pintype "passive"))
      (node (ref "R41") (pin "1") (pinfunction "1_1") (pintype "passive"))
      (node (ref "R42") (pin "1") (pinfunction "1_1") (pintype "passive"))
      (node (ref "R43") (pin "1") (pinfunction "1_1") (pintype "passive"))
      (node (ref "R44") (pin "1") (pinfunction "1_1") (pintype "passive"))
      (node (ref "U1") (pin "50") (pinfunction "VREF2_50") (pintype "passive"))
    )
    (net (code "41") (name "/VREG") (class "Default")
      (node (ref "C11") (pin "2") (pinfunction "2_2") (pintype "passive"))
      (node (ref "Q9") (pin "1") (pinfunction "E_1") (pintype "passive"))
      (node (ref "R28") (pin "2") (pinfunction "2_2") (pintype "passive"))
      (node (ref "R29") (pin "2") (pinfunction "2_2") (pintype "passive"))
      (node (ref "S2") (pin "3") (pinfunction "3_3") (pintype "passive"))
      (node (ref "S4") (pin "3") (pinfunction "3_3") (pintype "passive"))
      (node (ref "U1") (pin "48") (pinfunction "VREG_48") (pintype "passive"))
    )
    (net (code "42") (name "/WDT") (class "Default")
      (node (ref "P2") (pin "1") (pinfunction "1_1") (pintype "passive"))
      (node (ref "U1") (pin "56") (pinfunction "WDT_56") (pintype "passive"))
    )
    (net (code "43") (name "GND") (class "Default")
      (node (ref "BT7") (pin "2") (pinfunction "-_2") (pintype "passive"))
      (node (ref "C10") (pin "1") (pinfunction "1_1") (pintype "passive"))
      (node (ref "C11") (pin "1") (pinfunction "1_1") (pintype "passive"))
      (node (ref "C12") (pin "1") (pinfunction "1_1") (pintype "passive"))
      (node (ref "C13") (pin "1") (pinfunction "1_1") (pintype "passive"))
      (node (ref "C14") (pin "1") (pinfunction "1_1") (pintype "passive"))
      (node (ref "C15") (pin "1") (pinfunction "1_1") (pintype "passive"))
      (node (ref "C7") (pin "1") (pinfunction "1_1") (pintype "passive"))
      (node (ref "C9") (pin "1") (pinfunction "1_1") (pintype "passive"))
      (node (ref "J4") (pin "1") (pinfunction "1_1") (pintype "passive"))
      (node (ref "P1") (pin "1") (pinfunction "1_1") (pintype "passive"))
      (node (ref "P1") (pin "3") (pinfunction "3_3") (pintype "passive"))
      (node (ref "P1") (pin "5") (pinfunction "5_5") (pintype "passive"))
      (node (ref "P1") (pin "7") (pinfunction "7_7") (pintype "passive"))
      (node (ref "P2") (pin "8") (pinfunction "8_8") (pintype "passive"))
      (node (ref "P5") (pin "2") (pinfunction "2_2") (pintype "passive"))
      (node (ref "P8") (pin "1") (pinfunction "1_1") (pintype "passive"))
      (node (ref "P8") (pin "2") (pinfunction "2_2") (pintype "passive"))
      (node (ref "P9") (pin "1") (pinfunction "1_1") (pintype "passive"))
      (node (ref "R21") (pin "2") (pinfunction "2_2") (pintype "passive"))
      (node (ref "R31") (pin "2") (pinfunction "2_2") (pintype "passive"))
      (node (ref "R51") (pin "1") (pinfunction "1_1") (pintype "passive"))
      (node (ref "S2") (pin "1") (pinfunction "1_1") (pintype "passive"))
      (node (ref "S4") (pin "1") (pinfunction "1_1") (pintype "passive"))
      (node (ref "U1") (pin "38") (pinfunction "C0_38") (pintype "passive"))
      (node (ref "U1") (pin "59") (pinfunction "V-_59") (pintype "passive"))
      (node (ref "U1") (pin "60") (pinfunction "V-_60") (pintype "passive"))
      (node (ref "U1") (pin "65") (pinfunction "V-_65") (pintype "passive"))
    )
    (net (code "44") (name "Net-(C14-Pad2)") (class "Default")
      (node (ref "C14") (pin "2") (pinfunction "2_2") (pintype "passive"))
      (node (ref "R32") (pin "2") (pinfunction "2_2") (pintype "passive"))
      (node (ref "R33") (pin "1") (pinfunction "1_1") (pintype "passive"))
    )
    (net (code "45") (name "Net-(C15-Pad2)") (class "Default")
      (node (ref "C15") (pin "2") (pinfunction "2_2") (pintype "passive"))
      (node (ref "R34") (pin "2") (pinfunction "2_2") (pintype "passive"))
      (node (ref "R35") (pin "1") (pinfunction "1_1") (pintype "passive"))
    )
    (net (code "46") (name "Net-(D2-A)") (class "Default")
      (node (ref "D2") (pin "1") (pinfunction "A_1") (pintype "passive"))
      (node (ref "Q1") (pin "1") (pinfunction "D_1") (pintype "passive"))
      (node (ref "R3") (pin "1") (pinfunction "1_1") (pintype "passive"))
    )
    (net (code "47") (name "Net-(D2-K)") (class "Default")
      (node (ref "D2") (pin "2") (pinfunction "K_2") (pintype "passive"))
      (node (ref "R40") (pin "2") (pinfunction "2_2") (pintype "passive"))
    )
    (net (code "48") (name "Net-(D3-A)") (class "Default")
      (node (ref "D3") (pin "1") (pinfunction "A_1") (pintype "passive"))
      (node (ref "Q2") (pin "1") (pinfunction "D_1") (pintype "passive"))
      (node (ref "R6") (pin "1") (pinfunction "1_1") (pintype "passive"))
    )
    (net (code "49") (name "Net-(D3-K)") (class "Default")
      (node (ref "D3") (pin "2") (pinfunction "K_2") (pintype "passive"))
      (node (ref "R45") (pin "2") (pinfunction "2_2") (pintype "passive"))
    )
    (net (code "50") (name "Net-(D4-A)") (class "Default")
      (node (ref "D4") (pin "1") (pinfunction "A_1") (pintype "passive"))
      (node (ref "Q3") (pin "1") (pinfunction "D_1") (pintype "passive"))
      (node (ref "R9") (pin "1") (pinfunction "1_1") (pintype "passive"))
    )
    (net (code "51") (name "Net-(D4-K)") (class "Default")
      (node (ref "D4") (pin "2") (pinfunction "K_2") (pintype "passive"))
      (node (ref "R46") (pin "2") (pinfunction "2_2") (pintype "passive"))
    )
    (net (code "52") (name "Net-(D5-A)") (class "Default")
      (node (ref "D5") (pin "1") (pinfunction "A_1") (pintype "passive"))
      (node (ref "R22") (pin "2") (pinfunction "2_2") (pintype "passive"))
      (node (ref "S5") (pin "3") (pinfunction "3_3") (pintype "passive"))
    )
    (net (code "53") (name "Net-(D5-K)") (class "Default")
      (node (ref "D5") (pin "2") (pinfunction "K_2") (pintype "passive"))
      (node (ref "R23") (pin "1") (pinfunction "1_1") (pintype "passive"))
    )
    (net (code "54") (name "Net-(D6-A)") (class "Default")
      (node (ref "D6") (pin "1") (pinfunction "A_1") (pintype "passive"))
      (node (ref "Q4") (pin "1") (pinfunction "D_1") (pintype "passive"))
      (node (ref "R12") (pin "1") (pinfunction "1_1") (pintype "passive"))
    )
    (net (code "55") (name "Net-(D6-K)") (class "Default")
      (node (ref "D6") (pin "2") (pinfunction "K_2") (pintype "passive"))
      (node (ref "R48") (pin "2") (pinfunction "2_2") (pintype "passive"))
    )
    (net (code "56") (name "Net-(D7-A)") (class "Default")
      (node (ref "D7") (pin "1") (pinfunction "A_1") (pintype "passive"))
      (node (ref "Q5") (pin "1") (pinfunction "D_1") (pintype "passive"))
      (node (ref "R15") (pin "1") (pinfunction "1_1") (pintype "passive"))
    )
    (net (code "57") (name "Net-(D7-K)") (class "Default")
      (node (ref "D7") (pin "2") (pinfunction "K_2") (pintype "passive"))
      (node (ref "R49") (pin "2") (pinfunction "2_2") (pintype "passive"))
    )
    (net (code "58") (name "Net-(D8-A)") (class "Default")
      (node (ref "D8") (pin "1") (pinfunction "A_1") (pintype "passive"))
      (node (ref "Q6") (pin "1") (pinfunction "D_1") (pintype "passive"))
      (node (ref "R18") (pin "1") (pinfunction "1_1") (pintype "passive"))
    )
    (net (code "59") (name "Net-(D8-K)") (class "Default")
      (node (ref "D8") (pin "2") (pinfunction "K_2") (pintype "passive"))
      (node (ref "R50") (pin "2") (pinfunction "2_2") (pintype "passive"))
    )
    (net (code "60") (name "Net-(D9-A)") (class "Default")
      (node (ref "D9") (pin "1") (pinfunction "A_1") (pintype "passive"))
      (node (ref "Q7") (pin "1") (pinfunction "D_1") (pintype "passive"))
      (node (ref "R21") (pin "1") (pinfunction "1_1") (pintype "passive"))
    )
    (net (code "61") (name "Net-(D9-K)") (class "Default")
      (node (ref "D9") (pin "2") (pinfunction "K_2") (pintype "passive"))
      (node (ref "R51") (pin "2") (pinfunction "2_2") (pintype "passive"))
    )
    (net (code "62") (name "Net-(P2-Pad10)") (class "Default")
      (node (ref "P2") (pin "10") (pinfunction "10_10") (pintype "passive"))
      (node (ref "R38") (pin "2") (pinfunction "2_2") (pintype "passive"))
    )
    (net (code "63") (name "Net-(P2-Pad11)") (class "Default")
      (node (ref "P2") (pin "11") (pinfunction "11_11") (pintype "passive"))
      (node (ref "R39") (pin "2") (pinfunction "2_2") (pintype "passive"))
    )
    (net (code "64") (name "Net-(P2-Pad12)") (class "Default")
      (node (ref "P2") (pin "12") (pinfunction "12_12") (pintype "passive"))
      (node (ref "R37") (pin "1") (pinfunction "1_1") (pintype "passive"))
    )
    (net (code "65") (name "Net-(P2-Pad13)") (class "Default")
      (node (ref "P2") (pin "13") (pinfunction "13_13") (pintype "passive"))
      (node (ref "R36") (pin "1") (pinfunction "1_1") (pintype "passive"))
    )
    (net (code "66") (name "Net-(P5-Pad1)") (class "Default")
      (node (ref "P5") (pin "1") (pinfunction "1_1") (pintype "passive"))
      (node (ref "P9") (pin "2") (pinfunction "2_2") (pintype "passive"))
    )
    (net (code "67") (name "Net-(Q1-G)") (class "Default")
      (node (ref "Q1") (pin "2") (pinfunction "G_2") (pintype "passive"))
      (node (ref "R2") (pin "1") (pinfunction "1_1") (pintype "passive"))
    )
    (net (code "68") (name "Net-(Q2-G)") (class "Default")
      (node (ref "Q2") (pin "2") (pinfunction "G_2") (pintype "passive"))
      (node (ref "R5") (pin "1") (pinfunction "1_1") (pintype "passive"))
    )
    (net (code "69") (name "Net-(Q3-G)") (class "Default")
      (node (ref "Q3") (pin "2") (pinfunction "G_2") (pintype "passive"))
      (node (ref "R8") (pin "1") (pinfunction "1_1") (pintype "passive"))
    )
    (net (code "70") (name "Net-(Q4-G)") (class "Default")
      (node (ref "Q4") (pin "2") (pinfunction "G_2") (pintype "passive"))
      (node (ref "R11") (pin "1") (pinfunction "1_1") (pintype "passive"))
    )
    (net (code "71") (name "Net-(Q5-G)") (class "Default")
      (node (ref "Q5") (pin "2") (pinfunction "G_2") (pintype "passive"))
      (node (ref "R14") (pin "1") (pinfunction "1_1") (pintype "passive"))
    )
    (net (code "72") (name "Net-(Q6-G)") (class "Default")
      (node (ref "Q6") (pin "2") (pinfunction "G_2") (pintype "passive"))
      (node (ref "R17") (pin "1") (pinfunction "1_1") (pintype "passive"))
    )
    (net (code "73") (name "Net-(Q7-G)") (class "Default")
      (node (ref "Q7") (pin "2") (pinfunction "G_2") (pintype "passive"))
      (node (ref "R20") (pin "1") (pinfunction "1_1") (pintype "passive"))
    )
    (net (code "74") (name "Net-(Q9-C)") (class "Default")
      (node (ref "C10") (pin "2") (pinfunction "2_2") (pintype "passive"))
      (node (ref "Q9") (pin "3") (pinfunction "C_3") (pintype "passive"))
      (node (ref "R25") (pin "1") (pinfunction "1_1") (pintype "passive"))
    )
    (net (code "75") (name "Net-(R28-Pad1)") (class "Default")
      (node (ref "R28") (pin "1") (pinfunction "1_1") (pintype "passive"))
      (node (ref "S1") (pin "1") (pinfunction "1_1") (pintype "passive"))
    )
    (net (code "76") (name "Net-(R29-Pad1)") (class "Default")
      (node (ref "R29") (pin "1") (pinfunction "1_1") (pintype "passive"))
      (node (ref "S3") (pin "1") (pinfunction "1_1") (pintype "passive"))
    )
    (net (code "77") (name "Net-(R34-Pad1)") (class "Default")
      (node (ref "R34") (pin "1") (pinfunction "1_1") (pintype "passive"))
      (node (ref "S1") (pin "3") (pinfunction "3_3") (pintype "passive"))
      (node (ref "XFMR") (pin "9") (pinfunction "9_9") (pintype "passive"))
    )
    (net (code "78") (name "Net-(R35-Pad2)") (class "Default")
      (node (ref "R35") (pin "2") (pinfunction "2_2") (pintype "passive"))
      (node (ref "S3") (pin "3") (pinfunction "3_3") (pintype "passive"))
      (node (ref "XFMR") (pin "10") (pinfunction "10_10") (pintype "passive"))
    )
    (net (code "79") (name "Net-(U1-C13)") (class "Default")
      (node (ref "R24") (pin "2") (pinfunction "2_2") (pintype "passive"))
      (node (ref "U1") (pin "4") (pinfunction "C15_4") (pintype "passive"))
      (node (ref "U1") (pin "6") (pinfunction "C14_6") (pintype "passive"))
      (node (ref "U1") (pin "8") (pinfunction "C13_8") (pintype "passive"))
    )
    (net (code "80") (name "Net-(U1-DTEN)") (class "Default")
      (node (ref "S4") (pin "2") (pinfunction "2_2") (pintype "passive"))
      (node (ref "U1") (pin "52") (pinfunction "DTEN_52") (pintype "passive"))
    )
    (net (code "81") (name "Net-(U1-IBIAS)") (class "Default")
      (node (ref "R30") (pin "1") (pinfunction "1_1") (pintype "passive"))
      (node (ref "U1") (pin "57") (pinfunction "IBIAS_57") (pintype "passive"))
    )
    (net (code "82") (name "Net-(U1-ICMP)") (class "Default")
      (node (ref "R30") (pin "2") (pinfunction "2_2") (pintype "passive"))
      (node (ref "R31") (pin "1") (pinfunction "1_1") (pintype "passive"))
      (node (ref "U1") (pin "58") (pinfunction "ICMP_58") (pintype "passive"))
    )
    (net (code "83") (name "Net-(U1-IMB)") (class "Default")
      (node (ref "R33") (pin "2") (pinfunction "2_2") (pintype "passive"))
      (node (ref "U1") (pin "63") (pinfunction "IMB_63") (pintype "passive"))
      (node (ref "XFMR") (pin "7") (pinfunction "7_7") (pintype "passive"))
    )
    (net (code "84") (name "Net-(U1-IPB)") (class "Default")
      (node (ref "R32") (pin "1") (pinfunction "1_1") (pintype "passive"))
      (node (ref "U1") (pin "64") (pinfunction "IPB_64") (pintype "passive"))
      (node (ref "XFMR") (pin "6") (pinfunction "6_6") (pintype "passive"))
    )
    (net (code "85") (name "Net-(U1-ISOMD)") (class "Default")
      (node (ref "S2") (pin "2") (pinfunction "2_2") (pintype "passive"))
      (node (ref "U1") (pin "55") (pinfunction "ISOMD_55") (pintype "passive"))
    )
    (net (code "86") (name "Net-(U1-V+)") (class "Default")
      (node (ref "C9") (pin "2") (pinfunction "2_2") (pintype "passive"))
      (node (ref "R22") (pin "1") (pinfunction "1_1") (pintype "passive"))
      (node (ref "U1") (pin "1") (pinfunction "V+_1") (pintype "passive"))
    )
    (net (code "87") (name "VCC") (class "Default")
      (node (ref "BT1") (pin "1") (pinfunction "+_1") (pintype "passive"))
      (node (ref "J5") (pin "1") (pinfunction "1_1") (pintype "passive"))
      (node (ref "P10") (pin "1") (pinfunction "1_1") (pintype "passive"))
      (node (ref "P10") (pin "2") (pinfunction "2_2") (pintype "passive"))
      (node (ref "P11") (pin "1") (pinfunction "1_1") (pintype "passive"))
      (node (ref "P11") (pin "2") (pinfunction "2_2") (pintype "passive"))
      (node (ref "P2") (pin "9") (pinfunction "9_9") (pintype "passive"))
      (node (ref "P6") (pin "1") (pinfunction "1_1") (pintype "passive"))
      (node (ref "P6") (pin "2") (pinfunction "2_2") (pintype "passive"))
      (node (ref "P7") (pin "1") (pinfunction "1_1") (pintype "passive"))
      (node (ref "P7") (pin "2") (pinfunction "2_2") (pintype "passive"))
      (node (ref "Q1") (pin "3") (pinfunction "S_3") (pintype "passive"))
      (node (ref "R1") (pin "1") (pinfunction "1_1") (pintype "passive"))
      (node (ref "R24") (pin "1") (pinfunction "1_1") (pintype "passive"))
      (node (ref "R25") (pin "2") (pinfunction "2_2") (pintype "passive"))
      (node (ref "R26") (pin "1") (pinfunction "1_1") (pintype "passive"))
      (node (ref "R27") (pin "1") (pinfunction "1_1") (pintype "passive"))
      (node (ref "S5") (pin "2") (pinfunction "2_2") (pintype "passive"))
    )
    (net (code "88") (name "unconnected-(P2-Pad14)") (class "Default")
      (node (ref "P2") (pin "14") (pinfunction "14_14") (pintype "passive+no_connect"))
    )
    (net (code "89") (name "unconnected-(S5-Pad1)") (class "Default")
      (node (ref "S5") (pin "1") (pinfunction "1_1") (pintype "passive+no_connect"))
    )
    (net (code "90") (name "unconnected-(U1-NC-Pad2)") (class "Default")
      (node (ref "U1") (pin "2") (pinfunction "NC_2") (pintype "passive+no_connect"))
    )
    (net (code "91") (name "unconnected-(U1-NC-Pad3)") (class "Default")
      (node (ref "U1") (pin "3") (pinfunction "NC_3") (pintype "passive+no_connect"))
    )
    (net (code "92") (name "unconnected-(U1-NC-Pad14)") (class "Default")
      (node (ref "U1") (pin "14") (pinfunction "NC_14") (pintype "passive+no_connect"))
    )
    (net (code "93") (name "unconnected-(U1-NC-Pad15)") (class "Default")
      (node (ref "U1") (pin "15") (pinfunction "NC_15") (pintype "passive+no_connect"))
    )
    (net (code "94") (name "unconnected-(U1-NC-Pad26)") (class "Default")
      (node (ref "U1") (pin "26") (pinfunction "NC_26") (pintype "passive+no_connect"))
    )
    (net (code "95") (name "unconnected-(U1-NC-Pad27)") (class "Default")
      (node (ref "U1") (pin "27") (pinfunction "NC_27") (pintype "passive+no_connect"))
    )
    (net (code "96") (name "unconnected-(U1-S4-Pad31)") (class "Default")
      (node (ref "U1") (pin "31") (pinfunction "S4_31") (pintype "passive+no_connect"))
    )
    (net (code "97") (name "unconnected-(U1-S5-Pad29)") (class "Default")
      (node (ref "U1") (pin "29") (pinfunction "S5_29") (pintype "passive+no_connect"))
    )
    (net (code "98") (name "unconnected-(U1-S8-Pad21)") (class "Default")
      (node (ref "U1") (pin "21") (pinfunction "S8_21") (pintype "passive"))
    )
    (net (code "99") (name "unconnected-(U1-S9-Pad19)") (class "Default")
      (node (ref "U1") (pin "19") (pinfunction "S9_19") (pintype "passive+no_connect"))
    )
    (net (code "100") (name "unconnected-(U1-S10-Pad17)") (class "Default")
      (node (ref "U1") (pin "17") (pinfunction "S10_17") (pintype "passive+no_connect"))
    )
    (net (code "101") (name "unconnected-(U1-S13-Pad9)") (class "Default")
      (node (ref "U1") (pin "9") (pinfunction "S13_9") (pintype "passive+no_connect"))
    )
    (net (code "102") (name "unconnected-(U1-S14-Pad7)") (class "Default")
      (node (ref "U1") (pin "7") (pinfunction "S14_7") (pintype "passive+no_connect"))
    )
    (net (code "103") (name "unconnected-(U1-S15-Pad5)") (class "Default")
      (node (ref "U1") (pin "5") (pinfunction "S15_5") (pintype "passive+no_connect"))
    )
    (net (code "104") (name "unconnected-(XFMR-Pad3)") (class "Default")
      (node (ref "XFMR") (pin "3") (pinfunction "3_3") (pintype "passive+no_connect"))
    )
    (net (code "105") (name "unconnected-(XFMR-Pad8)") (class "Default")
      (node (ref "XFMR") (pin "8") (pinfunction "8_8") (pintype "passive+no_connect"))
    )
  )
)
